# Connections.net
KiCad netlist of a schematic drawn in Altium Designer
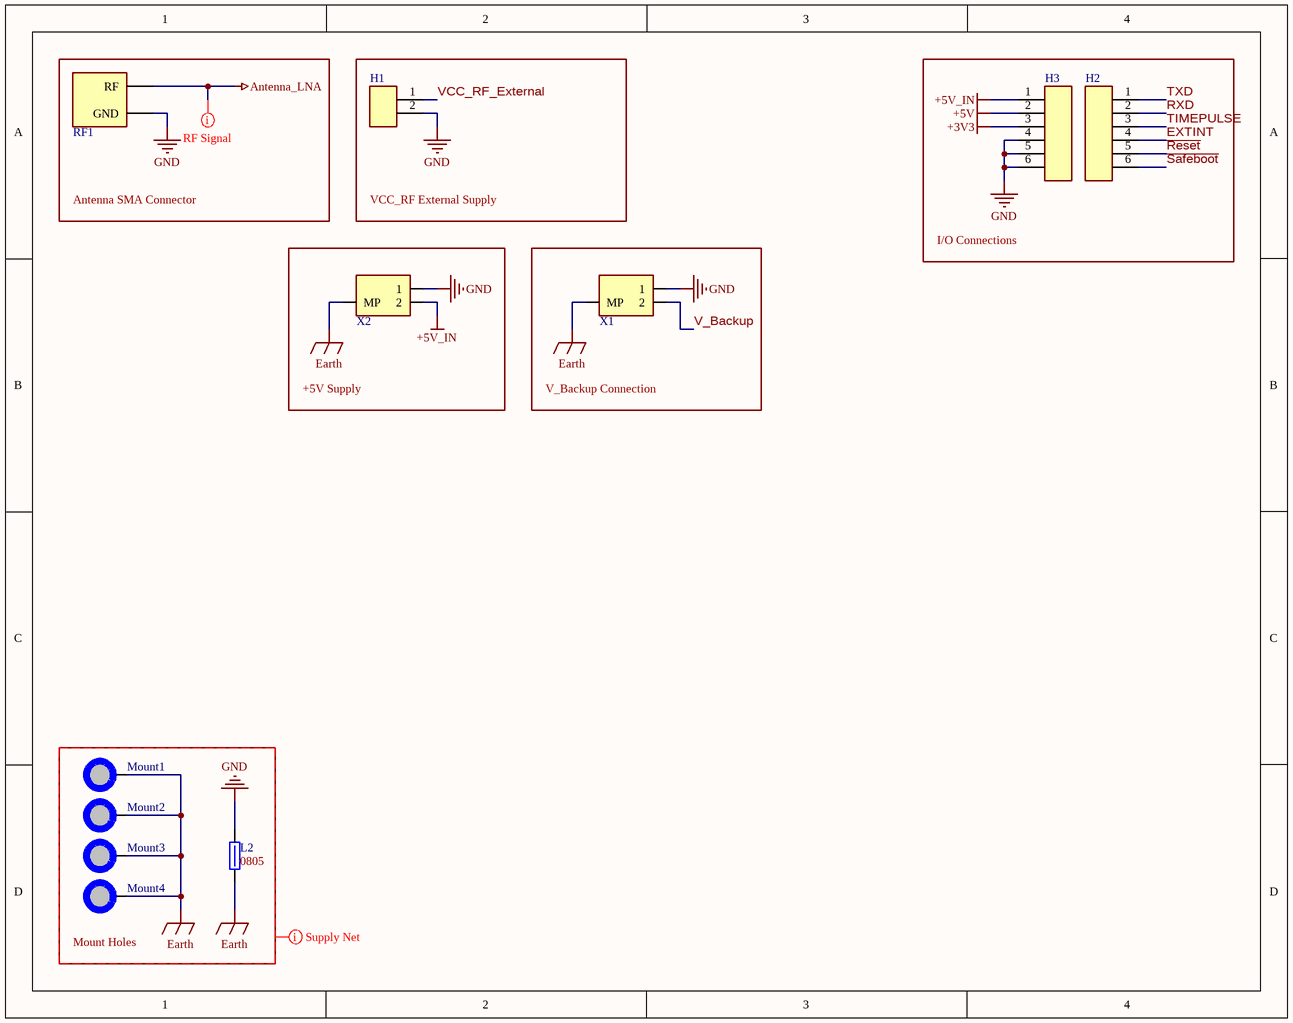
[diagram p0: Connections.SchDoc]

(export (version "E")
  (design (tool "Eeschema 10.0.6"))
  (components
    (comp (ref "H1")
      (value "1x2 Header")
      (footprint "[Header] 1x2 Male")
      (description "2.54mm pitch")
      (libsource (lib "Connectors") (part "[Header] 1x2 Male"))
    )
    (comp (ref "H2")
      (value "1x6 Header")
      (footprint "[Header] 1x6 Male")
      (description "2.54mm pitch")
      (libsource (lib "Connectors") (part "[Header] 1x6 Male"))
    )
    (comp (ref "H3")
      (value "1x6 Header")
      (footprint "[Header] 1x6 Male")
      (description "2.54mm pitch")
      (libsource (lib "") (part "[Header] 1x6 Male_1"))
    )
    (comp (ref "L2")
      (value "652-MH2029-300Y")
      (footprint "[Ferrite] SMD 0805")
      (fields (field (name "SIZE PACKAGE") "0805"))
      (libsource (lib "Ferrite Beads") (part "[Ferrite] SMD 0805 3A 30ohm"))
    )
    (comp (ref "Mount1")
      (value "M3 Mount Hole")
      (footprint "[Mount] M3 Mount Hole")
      (description "Place at least 4.5mm from board edge. Plated.")
      (libsource (lib "Mounts, Pads, Vias") (part "[Mount] M3 Mount Hole"))
    )
    (comp (ref "Mount2")
      (value "M3 Mount Hole")
      (footprint "[Mount] M3 Mount Hole")
      (description "Place at least 4.5mm from board edge. Plated.")
      (libsource (lib "Mounts, Pads, Vias") (part "[Mount] M3 Mount Hole"))
    )
    (comp (ref "Mount3")
      (value "M3 Mount Hole")
      (footprint "[Mount] M3 Mount Hole")
      (description "Place at least 4.5mm from board edge. Plated.")
      (libsource (lib "Mounts, Pads, Vias") (part "[Mount] M3 Mount Hole"))
    )
    (comp (ref "Mount4")
      (value "M3 Mount Hole")
      (footprint "[Mount] M3 Mount Hole")
      (description "Place at least 4.5mm from board edge. Plated.")
      (libsource (lib "Mounts, Pads, Vias") (part "[Mount] M3 Mount Hole"))
    )
    (comp (ref "RF1")
      (value "[SMA] 90deg Thru-Hole")
      (footprint "[SMA] 90deg Thru-Hole")
      (description "RFPC-SMA27-F")
      (libsource (lib "Connectors") (part "[SMA] 90deg Thru-Hole"))
    )
    (comp (ref "X1")
      (value "[Pheonix] 2pin 2.5mm pitch")
      (footprint "[Pheonix] 2pin 2.5mm pitch")
      (description "1778764")
      (libsource (lib "Connectors") (part "[Pheonix] 2pin 2.5mm pitch"))
    )
    (comp (ref "X2")
      (value "[Pheonix] 2pin 2.5mm pitch")
      (footprint "[Pheonix] 2pin 2.5mm pitch")
      (description "1778764")
      (libsource (lib "Connectors") (part "[Pheonix] 2pin 2.5mm pitch"))
    )
  )
  (nets
    (net (code "1") (name "+3V3") (class "Default") (node (ref "H3") (pin "3") (pintype "passive")))
    (net (code "2") (name "+5V") (class "Default") (node (ref "H3") (pin "2") (pintype "passive")))
    (net (code "3") (name "+5V_IN") (class "Default")
      (node (ref "H3") (pin "1") (pintype "passive"))
      (node (ref "X2") (pin "2") (pinfunction "2_2") (pintype "passive"))
    )
    (net (code "4") (name "/EXTINT") (class "Default") (node (ref "H2") (pin "4") (pintype "passive")))
    (net (code "5") (name "/RXD") (class "Default") (node (ref "H2") (pin "2") (pintype "passive")))
    (net (code "6") (name "/Reset") (class "Default") (node (ref "H2") (pin "5") (pintype "passive")))
    (net (code "7") (name "/Safeboot") (class "Default") (node (ref "H2") (pin "6") (pintype "passive")))
    (net (code "8") (name "/TIMEPULSE") (class "Default") (node (ref "H2") (pin "3") (pintype "passive")))
    (net (code "9") (name "/TXD") (class "Default") (node (ref "H2") (pin "1") (pintype "passive")))
    (net (code "10") (name "/VCC_RF_External") (class "Default")
      (node (ref "H1") (pin "1") (pintype "passive"))
    )
    (net (code "11") (name "/V_Backup") (class "Default")
      (node (ref "X1") (pin "2") (pinfunction "2_2") (pintype "passive"))
    )
    (net (code "12") (name "Antenna_LNA") (class "Default")
      (node (ref "RF1") (pin "1") (pinfunction "RF_1") (pintype "passive"))
    )
    (net (code "13") (name "Earth") (class "Default")
      (node (ref "L2") (pin "1") (pinfunction "1_1") (pintype "passive"))
      (node (ref "Mount1") (pin "1") (pintype "power_in"))
      (node (ref "Mount2") (pin "1") (pintype "power_in"))
      (node (ref "Mount3") (pin "1") (pintype "power_in"))
      (node (ref "Mount4") (pin "1") (pintype "power_in"))
      (node (ref "X1") (pin "MP") (pinfunction "MP_MP") (pintype "passive"))
      (node (ref "X2") (pin "MP") (pinfunction "MP_MP") (pintype "passive"))
    )
    (net (code "14") (name "GND") (class "Default")
      (node (ref "H1") (pin "2") (pintype "passive"))
      (node (ref "H3") (pin "4") (pintype "passive"))
      (node (ref "H3") (pin "5") (pintype "passive"))
      (node (ref "H3") (pin "6") (pintype "passive"))
      (node (ref "L2") (pin "2") (pinfunction "2_2") (pintype "passive"))
      (node (ref "RF1") (pin "2") (pinfunction "GND_2") (pintype "power_in"))
      (node (ref "X1") (pin "1") (pinfunction "1_1") (pintype "passive"))
      (node (ref "X2") (pin "1") (pinfunction "1_1") (pintype "passive"))
    )
  )
)
